# IO.net
KiCad netlist of a schematic drawn in Altium Designer
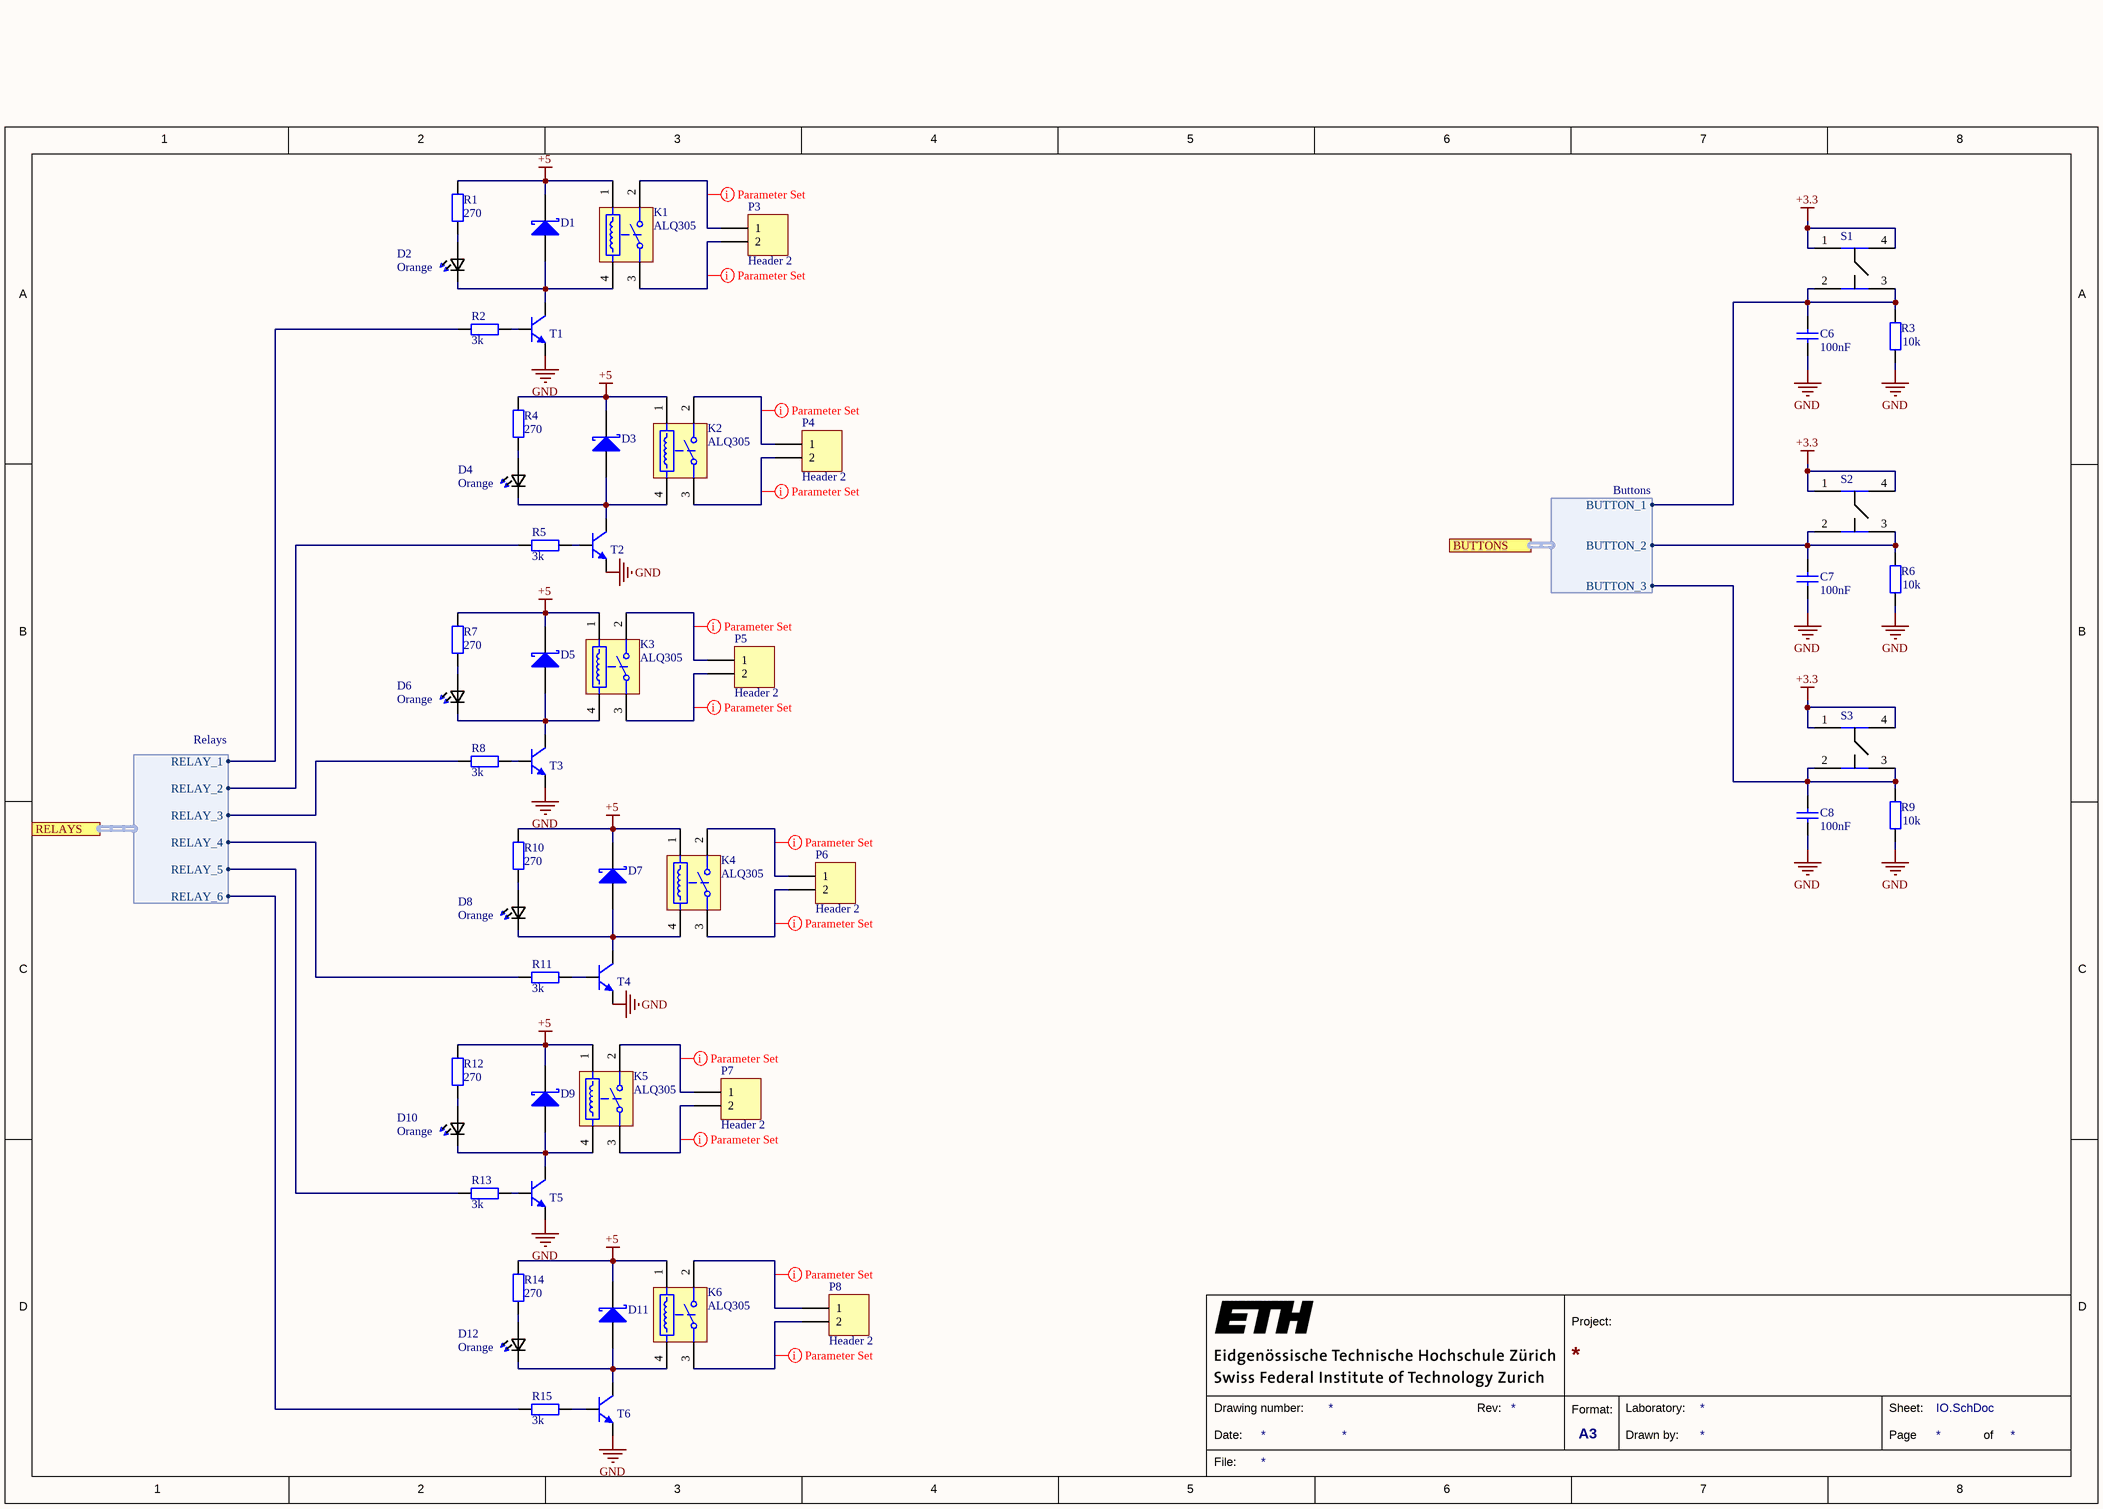
[diagram p0: IO.SchDoc]

(export (version "E")
  (design (tool "Eeschema 10.0.6"))
  (components
    (comp (ref "C6")
      (value "100nF")
      (footprint "CAP_0603i_1608m -N")
      (description "capacitor")
      (libsource (lib "IDSC std generic parts") (part "Cap"))
    )
    (comp (ref "C7")
      (value "100nF")
      (footprint "CAP_0603i_1608m -N")
      (description "capacitor")
      (libsource (lib "IDSC std generic parts") (part "Cap"))
    )
    (comp (ref "C8")
      (value "100nF")
      (footprint "CAP_0603i_1608m -N")
      (description "capacitor")
      (libsource (lib "IDSC std generic parts") (part "Cap"))
    )
    (comp (ref "D1")
      (value "Diode  Schottky")
      (footprint "SOD123")
      (description "Schottky Diode")
      (libsource (lib "IDSC std generic parts") (part "Diode  Schottky"))
    )
    (comp (ref "D2")
      (value "Orange")
      (footprint "*0603")
      (description "LED; SMD; 0603; orange; 45-90mcd; 1.6x0.8x0.55mm; 130Â°; 2Ã·2.4V; 20mA")
      (fields (field (name "MP") "LTST-C191KFKT") (field (name "DIGI-KEY_PART_NUMBER") "160-1445-1-ND"))
      (libsource (lib "Funk") (part "LTST-C191KFKT"))
    )
    (comp (ref "D3")
      (value "Diode  Schottky")
      (footprint "SOD123")
      (description "Schottky Diode")
      (libsource (lib "IDSC std generic parts") (part "Diode  Schottky"))
    )
    (comp (ref "D4")
      (value "Orange")
      (footprint "*0603")
      (description "LED; SMD; 0603; orange; 45-90mcd; 1.6x0.8x0.55mm; 130Â°; 2Ã·2.4V; 20mA")
      (fields (field (name "MP") "LTST-C191KFKT") (field (name "DIGI-KEY_PART_NUMBER") "160-1445-1-ND"))
      (libsource (lib "Funk") (part "LTST-C191KFKT"))
    )
    (comp (ref "D5")
      (value "Diode  Schottky")
      (footprint "SOD123")
      (description "Schottky Diode")
      (libsource (lib "IDSC std generic parts") (part "Diode  Schottky"))
    )
    (comp (ref "D6")
      (value "Orange")
      (footprint "*0603")
      (description "LED; SMD; 0603; orange; 45-90mcd; 1.6x0.8x0.55mm; 130Â°; 2Ã·2.4V; 20mA")
      (fields (field (name "MP") "LTST-C191KFKT") (field (name "DIGI-KEY_PART_NUMBER") "160-1445-1-ND"))
      (libsource (lib "Funk") (part "LTST-C191KFKT"))
    )
    (comp (ref "D7")
      (value "Diode  Schottky")
      (footprint "SOD123")
      (description "Schottky Diode")
      (libsource (lib "IDSC std generic parts") (part "Diode  Schottky"))
    )
    (comp (ref "D8")
      (value "Orange")
      (footprint "*0603")
      (description "LED; SMD; 0603; orange; 45-90mcd; 1.6x0.8x0.55mm; 130Â°; 2Ã·2.4V; 20mA")
      (fields (field (name "MP") "LTST-C191KFKT") (field (name "DIGI-KEY_PART_NUMBER") "160-1445-1-ND"))
      (libsource (lib "Funk") (part "LTST-C191KFKT"))
    )
    (comp (ref "D9")
      (value "Diode  Schottky")
      (footprint "SOD123")
      (description "Schottky Diode")
      (libsource (lib "IDSC std generic parts") (part "Diode  Schottky"))
    )
    (comp (ref "D10")
      (value "Orange")
      (footprint "*0603")
      (description "LED; SMD; 0603; orange; 45-90mcd; 1.6x0.8x0.55mm; 130Â°; 2Ã·2.4V; 20mA")
      (fields (field (name "MP") "LTST-C191KFKT") (field (name "DIGI-KEY_PART_NUMBER") "160-1445-1-ND"))
      (libsource (lib "Funk") (part "LTST-C191KFKT"))
    )
    (comp (ref "D11")
      (value "Diode  Schottky")
      (footprint "SOD123")
      (description "Schottky Diode")
      (libsource (lib "IDSC std generic parts") (part "Diode  Schottky"))
    )
    (comp (ref "D12")
      (value "Orange")
      (footprint "*0603")
      (description "LED; SMD; 0603; orange; 45-90mcd; 1.6x0.8x0.55mm; 130Â°; 2Ã·2.4V; 20mA")
      (fields (field (name "MP") "LTST-C191KFKT") (field (name "DIGI-KEY_PART_NUMBER") "160-1445-1-ND"))
      (libsource (lib "Funk") (part "LTST-C191KFKT"))
    )
    (comp (ref "K1")
      (value "ALQ305")
      (footprint "PNSC-LQ-4-2000x1000x1600_V")
      (fields (field (name "MANUFACTURER") "Panasonic"))
      (libsource (lib "Altium Content Vault") (part "PNSC-ALQ305-LQ-4-2000x1000x1600-4"))
    )
    (comp (ref "K2")
      (value "ALQ305")
      (footprint "PNSC-LQ-4-2000x1000x1600_V")
      (fields (field (name "MANUFACTURER") "Panasonic"))
      (libsource (lib "Altium Content Vault") (part "PNSC-ALQ305-LQ-4-2000x1000x1600-4"))
    )
    (comp (ref "K3")
      (value "ALQ305")
      (footprint "PNSC-LQ-4-2000x1000x1600_V")
      (fields (field (name "MANUFACTURER") "Panasonic"))
      (libsource (lib "Altium Content Vault") (part "PNSC-ALQ305-LQ-4-2000x1000x1600-4"))
    )
    (comp (ref "K4")
      (value "ALQ305")
      (footprint "PNSC-LQ-4-2000x1000x1600_V")
      (fields (field (name "MANUFACTURER") "Panasonic"))
      (libsource (lib "Altium Content Vault") (part "PNSC-ALQ305-LQ-4-2000x1000x1600-4"))
    )
    (comp (ref "K5")
      (value "ALQ305")
      (footprint "PNSC-LQ-4-2000x1000x1600_V")
      (fields (field (name "MANUFACTURER") "Panasonic"))
      (libsource (lib "Altium Content Vault") (part "PNSC-ALQ305-LQ-4-2000x1000x1600-4"))
    )
    (comp (ref "K6")
      (value "ALQ305")
      (footprint "PNSC-LQ-4-2000x1000x1600_V")
      (fields (field (name "MANUFACTURER") "Panasonic"))
      (libsource (lib "Altium Content Vault") (part "PNSC-ALQ305-LQ-4-2000x1000x1600-4"))
    )
    (comp (ref "P3")
      (value "Header 2")
      (footprint "3.5MM Phoenix Contact 1984617")
      (description "Header, 2-Pin")
      (libsource (lib "IDSC std connectors") (part "Header 2"))
    )
    (comp (ref "P4")
      (value "Header 2")
      (footprint "3.5MM Phoenix Contact 1984617")
      (description "Header, 2-Pin")
      (libsource (lib "IDSC std connectors") (part "Header 2"))
    )
    (comp (ref "P5")
      (value "Header 2")
      (footprint "3.5MM Phoenix Contact 1984617")
      (description "Header, 2-Pin")
      (libsource (lib "IDSC std connectors") (part "Header 2"))
    )
    (comp (ref "P6")
      (value "Header 2")
      (footprint "3.5MM Phoenix Contact 1984617")
      (description "Header, 2-Pin")
      (libsource (lib "IDSC std connectors") (part "Header 2"))
    )
    (comp (ref "P7")
      (value "Header 2")
      (footprint "3.5MM Phoenix Contact 1984617")
      (description "Header, 2-Pin")
      (libsource (lib "IDSC std connectors") (part "Header 2"))
    )
    (comp (ref "P8")
      (value "Header 2")
      (footprint "3.5MM Phoenix Contact 1984617")
      (description "Header, 2-Pin")
      (libsource (lib "IDSC std connectors") (part "Header 2"))
    )
    (comp (ref "R1")
      (value "270")
      (footprint "RES_0603i_1608m -N")
      (description "Resistor")
      (libsource (lib "") (part "Res_1"))
    )
    (comp (ref "R2")
      (value "3k")
      (footprint "RES_0603i_1608m -N")
      (description "Resistor")
      (libsource (lib "IDSC std generic parts") (part "Res"))
    )
    (comp (ref "R3")
      (value "10k")
      (footprint "RES_0603i_1608m -N")
      (description "Resistor")
      (libsource (lib "") (part "Res_1"))
    )
    (comp (ref "R4")
      (value "270")
      (footprint "RES_0603i_1608m -N")
      (description "Resistor")
      (libsource (lib "") (part "Res_1"))
    )
    (comp (ref "R5")
      (value "3k")
      (footprint "RES_0603i_1608m -N")
      (description "Resistor")
      (libsource (lib "IDSC std generic parts") (part "Res"))
    )
    (comp (ref "R6")
      (value "10k")
      (footprint "RES_0603i_1608m -N")
      (description "Resistor")
      (libsource (lib "") (part "Res_1"))
    )
    (comp (ref "R7")
      (value "270")
      (footprint "RES_0603i_1608m -N")
      (description "Resistor")
      (libsource (lib "") (part "Res_1"))
    )
    (comp (ref "R8")
      (value "3k")
      (footprint "RES_0603i_1608m -N")
      (description "Resistor")
      (libsource (lib "IDSC std generic parts") (part "Res"))
    )
    (comp (ref "R9")
      (value "10k")
      (footprint "RES_0603i_1608m -N")
      (description "Resistor")
      (libsource (lib "") (part "Res_1"))
    )
    (comp (ref "R10")
      (value "270")
      (footprint "RES_0603i_1608m -N")
      (description "Resistor")
      (libsource (lib "") (part "Res_1"))
    )
    (comp (ref "R11")
      (value "3k")
      (footprint "RES_0603i_1608m -N")
      (description "Resistor")
      (libsource (lib "IDSC std generic parts") (part "Res"))
    )
    (comp (ref "R12")
      (value "270")
      (footprint "RES_0603i_1608m -N")
      (description "Resistor")
      (libsource (lib "") (part "Res_1"))
    )
    (comp (ref "R13")
      (value "3k")
      (footprint "RES_0603i_1608m -N")
      (description "Resistor")
      (libsource (lib "IDSC std generic parts") (part "Res"))
    )
    (comp (ref "R14")
      (value "270")
      (footprint "RES_0603i_1608m -N")
      (description "Resistor")
      (libsource (lib "") (part "Res_1"))
    )
    (comp (ref "R15")
      (value "3k")
      (footprint "RES_0603i_1608m -N")
      (description "Resistor")
      (libsource (lib "IDSC std generic parts") (part "Res"))
    )
    (comp (ref "S1")
      (value "EVQ-Q2U02W")
      (footprint "EVQQ2")
      (description "White Button Tactile Switch, Single Pole Single Throw (SPST) 20 mA @ 15 V dc 0.7mm")
      (fields (field (name "MOUSER PART NUMBER") "667-EVQ-Q2U02W"))
      (libsource (lib "LIB") (part "EVQ-Q2U02W"))
    )
    (comp (ref "S2")
      (value "EVQ-Q2U02W")
      (footprint "EVQQ2")
      (description "White Button Tactile Switch, Single Pole Single Throw (SPST) 20 mA @ 15 V dc 0.7mm")
      (fields (field (name "MOUSER PART NUMBER") "667-EVQ-Q2U02W"))
      (libsource (lib "LIB") (part "EVQ-Q2U02W"))
    )
    (comp (ref "S3")
      (value "EVQ-Q2U02W")
      (footprint "EVQQ2")
      (description "White Button Tactile Switch, Single Pole Single Throw (SPST) 20 mA @ 15 V dc 0.7mm")
      (fields (field (name "MOUSER PART NUMBER") "667-EVQ-Q2U02W"))
      (libsource (lib "LIB") (part "EVQ-Q2U02W"))
    )
    (comp (ref "T1")
      (value "Part Number: MMBT3904-7-F")
      (footprint "SOT-23-M")
      (description "No Description Available")
      (fields
        (field (name "MANUFACTURER_PART_NUMBER") "MMBT3904-7-F")
        (field (name "COPYRIGHT") "Copyright (C) 2018 Accelerated Designs. All rights reserved")
      )
      (libsource (lib "Funk") (part "MMBT3904-7-F"))
    )
    (comp (ref "T2")
      (value "Part Number: MMBT3904-7-F")
      (footprint "SOT-23-M")
      (description "No Description Available")
      (fields
        (field (name "MANUFACTURER_PART_NUMBER") "MMBT3904-7-F")
        (field (name "COPYRIGHT") "Copyright (C) 2018 Accelerated Designs. All rights reserved")
      )
      (libsource (lib "Funk") (part "MMBT3904-7-F"))
    )
    (comp (ref "T3")
      (value "Part Number: MMBT3904-7-F")
      (footprint "SOT-23-M")
      (description "No Description Available")
      (fields
        (field (name "MANUFACTURER_PART_NUMBER") "MMBT3904-7-F")
        (field (name "COPYRIGHT") "Copyright (C) 2018 Accelerated Designs. All rights reserved")
      )
      (libsource (lib "Funk") (part "MMBT3904-7-F"))
    )
    (comp (ref "T4")
      (value "Part Number: MMBT3904-7-F")
      (footprint "SOT-23-M")
      (description "No Description Available")
      (fields
        (field (name "MANUFACTURER_PART_NUMBER") "MMBT3904-7-F")
        (field (name "COPYRIGHT") "Copyright (C) 2018 Accelerated Designs. All rights reserved")
      )
      (libsource (lib "Funk") (part "MMBT3904-7-F"))
    )
    (comp (ref "T5")
      (value "Part Number: MMBT3904-7-F")
      (footprint "SOT-23-M")
      (description "No Description Available")
      (fields
        (field (name "MANUFACTURER_PART_NUMBER") "MMBT3904-7-F")
        (field (name "COPYRIGHT") "Copyright (C) 2018 Accelerated Designs. All rights reserved")
      )
      (libsource (lib "Funk") (part "MMBT3904-7-F"))
    )
    (comp (ref "T6")
      (value "Part Number: MMBT3904-7-F")
      (footprint "SOT-23-M")
      (description "No Description Available")
      (fields
        (field (name "MANUFACTURER_PART_NUMBER") "MMBT3904-7-F")
        (field (name "COPYRIGHT") "Copyright (C) 2018 Accelerated Designs. All rights reserved")
      )
      (libsource (lib "Funk") (part "MMBT3904-7-F"))
    )
  )
  (nets
    (net (code "3") (name "+3.3") (class "Default")
      (node (ref "S1") (pin "1") (pinfunction "NO_1_1") (pintype "passive"))
      (node (ref "S1") (pin "4") (pinfunction "NO_2_4") (pintype "passive"))
      (node (ref "S2") (pin "1") (pinfunction "NO_1_1") (pintype "passive"))
      (node (ref "S2") (pin "4") (pinfunction "NO_2_4") (pintype "passive"))
      (node (ref "S3") (pin "1") (pinfunction "NO_1_1") (pintype "passive"))
      (node (ref "S3") (pin "4") (pinfunction "NO_2_4") (pintype "passive"))
    )
    (net (code "4") (name "+5") (class "Default")
      (node (ref "D1") (pin "2") (pinfunction "K_2") (pintype "passive"))
      (node (ref "D11") (pin "2") (pinfunction "K_2") (pintype "passive"))
      (node (ref "D3") (pin "2") (pinfunction "K_2") (pintype "passive"))
      (node (ref "D5") (pin "2") (pinfunction "K_2") (pintype "passive"))
      (node (ref "D7") (pin "2") (pinfunction "K_2") (pintype "passive"))
      (node (ref "D9") (pin "2") (pinfunction "K_2") (pintype "passive"))
      (node (ref "K1") (pin "1") (pinfunction "1_1") (pintype "passive"))
      (node (ref "K2") (pin "1") (pinfunction "1_1") (pintype "passive"))
      (node (ref "K3") (pin "1") (pinfunction "1_1") (pintype "passive"))
      (node (ref "K4") (pin "1") (pinfunction "1_1") (pintype "passive"))
      (node (ref "K5") (pin "1") (pinfunction "1_1") (pintype "passive"))
      (node (ref "K6") (pin "1") (pinfunction "1_1") (pintype "passive"))
      (node (ref "R1") (pin "2") (pinfunction "2_2") (pintype "passive"))
      (node (ref "R10") (pin "2") (pinfunction "2_2") (pintype "passive"))
      (node (ref "R12") (pin "2") (pinfunction "2_2") (pintype "passive"))
      (node (ref "R14") (pin "2") (pinfunction "2_2") (pintype "passive"))
      (node (ref "R4") (pin "2") (pinfunction "2_2") (pintype "passive"))
      (node (ref "R7") (pin "2") (pinfunction "2_2") (pintype "passive"))
    )
    (net (code "5") (name "/BUTTON_1") (class "Default")
      (node (ref "C6") (pin "2") (pinfunction "2_2") (pintype "passive"))
      (node (ref "R3") (pin "2") (pinfunction "2_2") (pintype "passive"))
      (node (ref "S1") (pin "2") (pinfunction "COM_1_2") (pintype "passive"))
      (node (ref "S1") (pin "3") (pinfunction "COM_2_3") (pintype "passive"))
    )
    (net (code "6") (name "/BUTTON_2") (class "Default")
      (node (ref "C7") (pin "2") (pinfunction "2_2") (pintype "passive"))
      (node (ref "R6") (pin "2") (pinfunction "2_2") (pintype "passive"))
      (node (ref "S2") (pin "2") (pinfunction "COM_1_2") (pintype "passive"))
      (node (ref "S2") (pin "3") (pinfunction "COM_2_3") (pintype "passive"))
    )
    (net (code "7") (name "/BUTTON_3") (class "Default")
      (node (ref "C8") (pin "2") (pinfunction "2_2") (pintype "passive"))
      (node (ref "R9") (pin "2") (pinfunction "2_2") (pintype "passive"))
      (node (ref "S3") (pin "2") (pinfunction "COM_1_2") (pintype "passive"))
      (node (ref "S3") (pin "3") (pinfunction "COM_2_3") (pintype "passive"))
    )
    (net (code "8") (name "/RELAY_1") (class "Default")
      (node (ref "R2") (pin "2") (pinfunction "2_2") (pintype "passive"))
    )
    (net (code "9") (name "/RELAY_2") (class "Default")
      (node (ref "R5") (pin "2") (pinfunction "2_2") (pintype "passive"))
    )
    (net (code "10") (name "/RELAY_3") (class "Default")
      (node (ref "R8") (pin "2") (pinfunction "2_2") (pintype "passive"))
    )
    (net (code "11") (name "/RELAY_4") (class "Default")
      (node (ref "R11") (pin "2") (pinfunction "2_2") (pintype "passive"))
    )
    (net (code "12") (name "/RELAY_5") (class "Default")
      (node (ref "R13") (pin "2") (pinfunction "2_2") (pintype "passive"))
    )
    (net (code "13") (name "/RELAY_6") (class "Default")
      (node (ref "R15") (pin "2") (pinfunction "2_2") (pintype "passive"))
    )
    (net (code "16") (name "GND") (class "Default")
      (node (ref "C6") (pin "1") (pinfunction "1_1") (pintype "passive"))
      (node (ref "C7") (pin "1") (pinfunction "1_1") (pintype "passive"))
      (node (ref "C8") (pin "1") (pinfunction "1_1") (pintype "passive"))
      (node (ref "R3") (pin "1") (pinfunction "1_1") (pintype "passive"))
      (node (ref "R6") (pin "1") (pinfunction "1_1") (pintype "passive"))
      (node (ref "R9") (pin "1") (pinfunction "1_1") (pintype "passive"))
      (node (ref "T1") (pin "2") (pinfunction "E_2") (pintype "passive"))
      (node (ref "T2") (pin "2") (pinfunction "E_2") (pintype "passive"))
      (node (ref "T3") (pin "2") (pinfunction "E_2") (pintype "passive"))
      (node (ref "T4") (pin "2") (pinfunction "E_2") (pintype "passive"))
      (node (ref "T5") (pin "2") (pinfunction "E_2") (pintype "passive"))
      (node (ref "T6") (pin "2") (pinfunction "E_2") (pintype "passive"))
    )
    (net (code "17") (name "Net-(D1-A)") (class "Default")
      (node (ref "D1") (pin "1") (pinfunction "A_1") (pintype "passive"))
      (node (ref "D2") (pin "1") (pinfunction "K2_1") (pintype "passive"))
      (node (ref "K1") (pin "4") (pinfunction "4_4") (pintype "passive"))
      (node (ref "T1") (pin "3") (pinfunction "C_3") (pintype "passive"))
    )
    (net (code "18") (name "Net-(D2-A2)") (class "Default")
      (node (ref "D2") (pin "2") (pinfunction "A2_2") (pintype "passive"))
      (node (ref "R1") (pin "1") (pinfunction "1_1") (pintype "passive"))
    )
    (net (code "19") (name "Net-(D3-A)") (class "Default")
      (node (ref "D3") (pin "1") (pinfunction "A_1") (pintype "passive"))
      (node (ref "D4") (pin "1") (pinfunction "K2_1") (pintype "passive"))
      (node (ref "K2") (pin "4") (pinfunction "4_4") (pintype "passive"))
      (node (ref "T2") (pin "3") (pinfunction "C_3") (pintype "passive"))
    )
    (net (code "20") (name "Net-(D4-A2)") (class "Default")
      (node (ref "D4") (pin "2") (pinfunction "A2_2") (pintype "passive"))
      (node (ref "R4") (pin "1") (pinfunction "1_1") (pintype "passive"))
    )
    (net (code "21") (name "Net-(D5-A)") (class "Default")
      (node (ref "D5") (pin "1") (pinfunction "A_1") (pintype "passive"))
      (node (ref "D6") (pin "1") (pinfunction "K2_1") (pintype "passive"))
      (node (ref "K3") (pin "4") (pinfunction "4_4") (pintype "passive"))
      (node (ref "T3") (pin "3") (pinfunction "C_3") (pintype "passive"))
    )
    (net (code "22") (name "Net-(D6-A2)") (class "Default")
      (node (ref "D6") (pin "2") (pinfunction "A2_2") (pintype "passive"))
      (node (ref "R7") (pin "1") (pinfunction "1_1") (pintype "passive"))
    )
    (net (code "23") (name "Net-(D7-A)") (class "Default")
      (node (ref "D7") (pin "1") (pinfunction "A_1") (pintype "passive"))
      (node (ref "D8") (pin "1") (pinfunction "K2_1") (pintype "passive"))
      (node (ref "K4") (pin "4") (pinfunction "4_4") (pintype "passive"))
      (node (ref "T4") (pin "3") (pinfunction "C_3") (pintype "passive"))
    )
    (net (code "24") (name "Net-(D8-A2)") (class "Default")
      (node (ref "D8") (pin "2") (pinfunction "A2_2") (pintype "passive"))
      (node (ref "R10") (pin "1") (pinfunction "1_1") (pintype "passive"))
    )
    (net (code "25") (name "Net-(D10-A2)") (class "Default")
      (node (ref "D10") (pin "2") (pinfunction "A2_2") (pintype "passive"))
      (node (ref "R12") (pin "1") (pinfunction "1_1") (pintype "passive"))
    )
    (net (code "26") (name "Net-(D10-K2)") (class "Default")
      (node (ref "D10") (pin "1") (pinfunction "K2_1") (pintype "passive"))
      (node (ref "D9") (pin "1") (pinfunction "A_1") (pintype "passive"))
      (node (ref "K5") (pin "4") (pinfunction "4_4") (pintype "passive"))
      (node (ref "T5") (pin "3") (pinfunction "C_3") (pintype "passive"))
    )
    (net (code "27") (name "Net-(D11-A)") (class "Default")
      (node (ref "D11") (pin "1") (pinfunction "A_1") (pintype "passive"))
      (node (ref "D12") (pin "1") (pinfunction "K2_1") (pintype "passive"))
      (node (ref "K6") (pin "4") (pinfunction "4_4") (pintype "passive"))
      (node (ref "T6") (pin "3") (pinfunction "C_3") (pintype "passive"))
    )
    (net (code "28") (name "Net-(D12-A2)") (class "Default")
      (node (ref "D12") (pin "2") (pinfunction "A2_2") (pintype "passive"))
      (node (ref "R14") (pin "1") (pinfunction "1_1") (pintype "passive"))
    )
    (net (code "29") (name "Net-(K1-COM)") (class "Default")
      (node (ref "K1") (pin "3") (pinfunction "COM_3") (pintype "passive"))
      (node (ref "P3") (pin "2") (pinfunction "2_2") (pintype "passive"))
    )
    (net (code "30") (name "Net-(K1-NO)") (class "Default")
      (node (ref "K1") (pin "2") (pinfunction "NO_2") (pintype "passive"))
      (node (ref "P3") (pin "1") (pinfunction "1_1") (pintype "passive"))
    )
    (net (code "31") (name "Net-(K2-COM)") (class "Default")
      (node (ref "K2") (pin "3") (pinfunction "COM_3") (pintype "passive"))
      (node (ref "P4") (pin "2") (pinfunction "2_2") (pintype "passive"))
    )
    (net (code "32") (name "Net-(K2-NO)") (class "Default")
      (node (ref "K2") (pin "2") (pinfunction "NO_2") (pintype "passive"))
      (node (ref "P4") (pin "1") (pinfunction "1_1") (pintype "passive"))
    )
    (net (code "33") (name "Net-(K3-COM)") (class "Default")
      (node (ref "K3") (pin "3") (pinfunction "COM_3") (pintype "passive"))
      (node (ref "P5") (pin "2") (pinfunction "2_2") (pintype "passive"))
    )
    (net (code "34") (name "Net-(K3-NO)") (class "Default")
      (node (ref "K3") (pin "2") (pinfunction "NO_2") (pintype "passive"))
      (node (ref "P5") (pin "1") (pinfunction "1_1") (pintype "passive"))
    )
    (net (code "35") (name "Net-(K4-COM)") (class "Default")
      (node (ref "K4") (pin "3") (pinfunction "COM_3") (pintype "passive"))
      (node (ref "P6") (pin "2") (pinfunction "2_2") (pintype "passive"))
    )
    (net (code "36") (name "Net-(K4-NO)") (class "Default")
      (node (ref "K4") (pin "2") (pinfunction "NO_2") (pintype "passive"))
      (node (ref "P6") (pin "1") (pinfunction "1_1") (pintype "passive"))
    )
    (net (code "37") (name "Net-(K5-COM)") (class "Default")
      (node (ref "K5") (pin "3") (pinfunction "COM_3") (pintype "passive"))
      (node (ref "P7") (pin "2") (pinfunction "2_2") (pintype "passive"))
    )
    (net (code "38") (name "Net-(K5-NO)") (class "Default")
      (node (ref "K5") (pin "2") (pinfunction "NO_2") (pintype "passive"))
      (node (ref "P7") (pin "1") (pinfunction "1_1") (pintype "passive"))
    )
    (net (code "39") (name "Net-(K6-COM)") (class "Default")
      (node (ref "K6") (pin "3") (pinfunction "COM_3") (pintype "passive"))
      (node (ref "P8") (pin "2") (pinfunction "2_2") (pintype "passive"))
    )
    (net (code "40") (name "Net-(K6-NO)") (class "Default")
      (node (ref "K6") (pin "2") (pinfunction "NO_2") (pintype "passive"))
      (node (ref "P8") (pin "1") (pinfunction "1_1") (pintype "passive"))
    )
    (net (code "41") (name "Net-(T1-B)") (class "Default")
      (node (ref "R2") (pin "1") (pinfunction "1_1") (pintype "passive"))
      (node (ref "T1") (pin "1") (pinfunction "B_1") (pintype "passive"))
    )
    (net (code "42") (name "Net-(T2-B)") (class "Default")
      (node (ref "R5") (pin "1") (pinfunction "1_1") (pintype "passive"))
      (node (ref "T2") (pin "1") (pinfunction "B_1") (pintype "passive"))
    )
    (net (code "43") (name "Net-(T3-B)") (class "Default")
      (node (ref "R8") (pin "1") (pinfunction "1_1") (pintype "passive"))
      (node (ref "T3") (pin "1") (pinfunction "B_1") (pintype "passive"))
    )
    (net (code "44") (name "Net-(T4-B)") (class "Default")
      (node (ref "R11") (pin "1") (pinfunction "1_1") (pintype "passive"))
      (node (ref "T4") (pin "1") (pinfunction "B_1") (pintype "passive"))
    )
    (net (code "45") (name "Net-(T5-B)") (class "Default")
      (node (ref "R13") (pin "1") (pinfunction "1_1") (pintype "passive"))
      (node (ref "T5") (pin "1") (pinfunction "B_1") (pintype "passive"))
    )
    (net (code "46") (name "Net-(T6-B)") (class "Default")
      (node (ref "R15") (pin "1") (pinfunction "1_1") (pintype "passive"))
      (node (ref "T6") (pin "1") (pinfunction "B_1") (pintype "passive"))
    )
  )
)
